# vesc_can.net
KiCad netlist of a schematic drawn in Altium Designer
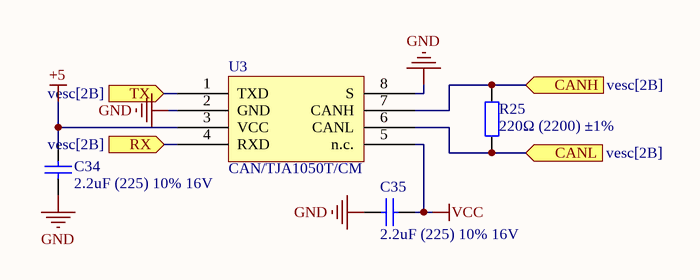
[diagram p0: vesc_can.SchDoc]

(export (version "E")
  (design (tool "Eeschema 10.0.6"))
  (components
    (comp (ref "C34")
      (value "2.2uF (225) 10% 16V")
      (footprint "0603_C")
      (description "贴片电容")
      (libsource (lib "Miscellaneous Devices LC") (part "0603 2.2uF (225) 10% 16V"))
    )
    (comp (ref "C35")
      (value "2.2uF (225) 10% 16V")
      (footprint "0603_C")
      (description "贴片电容")
      (libsource (lib "Miscellaneous Devices LC") (part "0603 2.2uF (225) 10% 16V"))
    )
    (comp (ref "R25")
      (value "220Ω (2200) ±1%")
      (footprint "0603_R")
      (description "贴片电阻")
      (libsource (lib "Miscellaneous Devices LC") (part "0603 220Ω (2200) 1%"))
    )
    (comp (ref "U3")
      (value "CAN/TJA1050T/CM")
      (footprint "SOIC-8_150mil")
      (description "CAN")
      (libsource (lib "Miscellaneous Devices LC") (part "CAN/TJA1050T/CM_[C6952]"))
    )
  )
  (nets
    (net (code "1") (name "+5") (class "Default")
      (node (ref "C34") (pin "2") (pinfunction "2_2") (pintype "passive"))
      (node (ref "U3") (pin "3") (pinfunction "VCC_3") (pintype "passive"))
    )
    (net (code "2") (name "/CANH") (class "Default")
      (node (ref "R25") (pin "2") (pinfunction "2_2") (pintype "passive"))
      (node (ref "U3") (pin "7") (pinfunction "CANH_7") (pintype "passive"))
    )
    (net (code "3") (name "/CANL") (class "Default")
      (node (ref "R25") (pin "1") (pinfunction "1_1") (pintype "passive"))
      (node (ref "U3") (pin "6") (pinfunction "CANL_6") (pintype "passive"))
    )
    (net (code "4") (name "/RX") (class "Default")
      (node (ref "U3") (pin "4") (pinfunction "RXD_4") (pintype "passive"))
    )
    (net (code "5") (name "/TX") (class "Default")
      (node (ref "U3") (pin "1") (pinfunction "TXD_1") (pintype "passive"))
    )
    (net (code "6") (name "GND") (class "Default")
      (node (ref "C34") (pin "1") (pinfunction "1_1") (pintype "passive"))
      (node (ref "C35") (pin "1") (pinfunction "1_1") (pintype "passive"))
      (node (ref "U3") (pin "2") (pinfunction "GND_2") (pintype "passive"))
      (node (ref "U3") (pin "8") (pinfunction "S_8") (pintype "passive"))
    )
    (net (code "7") (name "VCC") (class "Default")
      (node (ref "C35") (pin "2") (pinfunction "2_2") (pintype "passive"))
      (node (ref "U3") (pin "5") (pinfunction "n.c._5") (pintype "passive"))
    )
  )
)
